# R203X.net
KiCad netlist of a schematic drawn in EAGLE
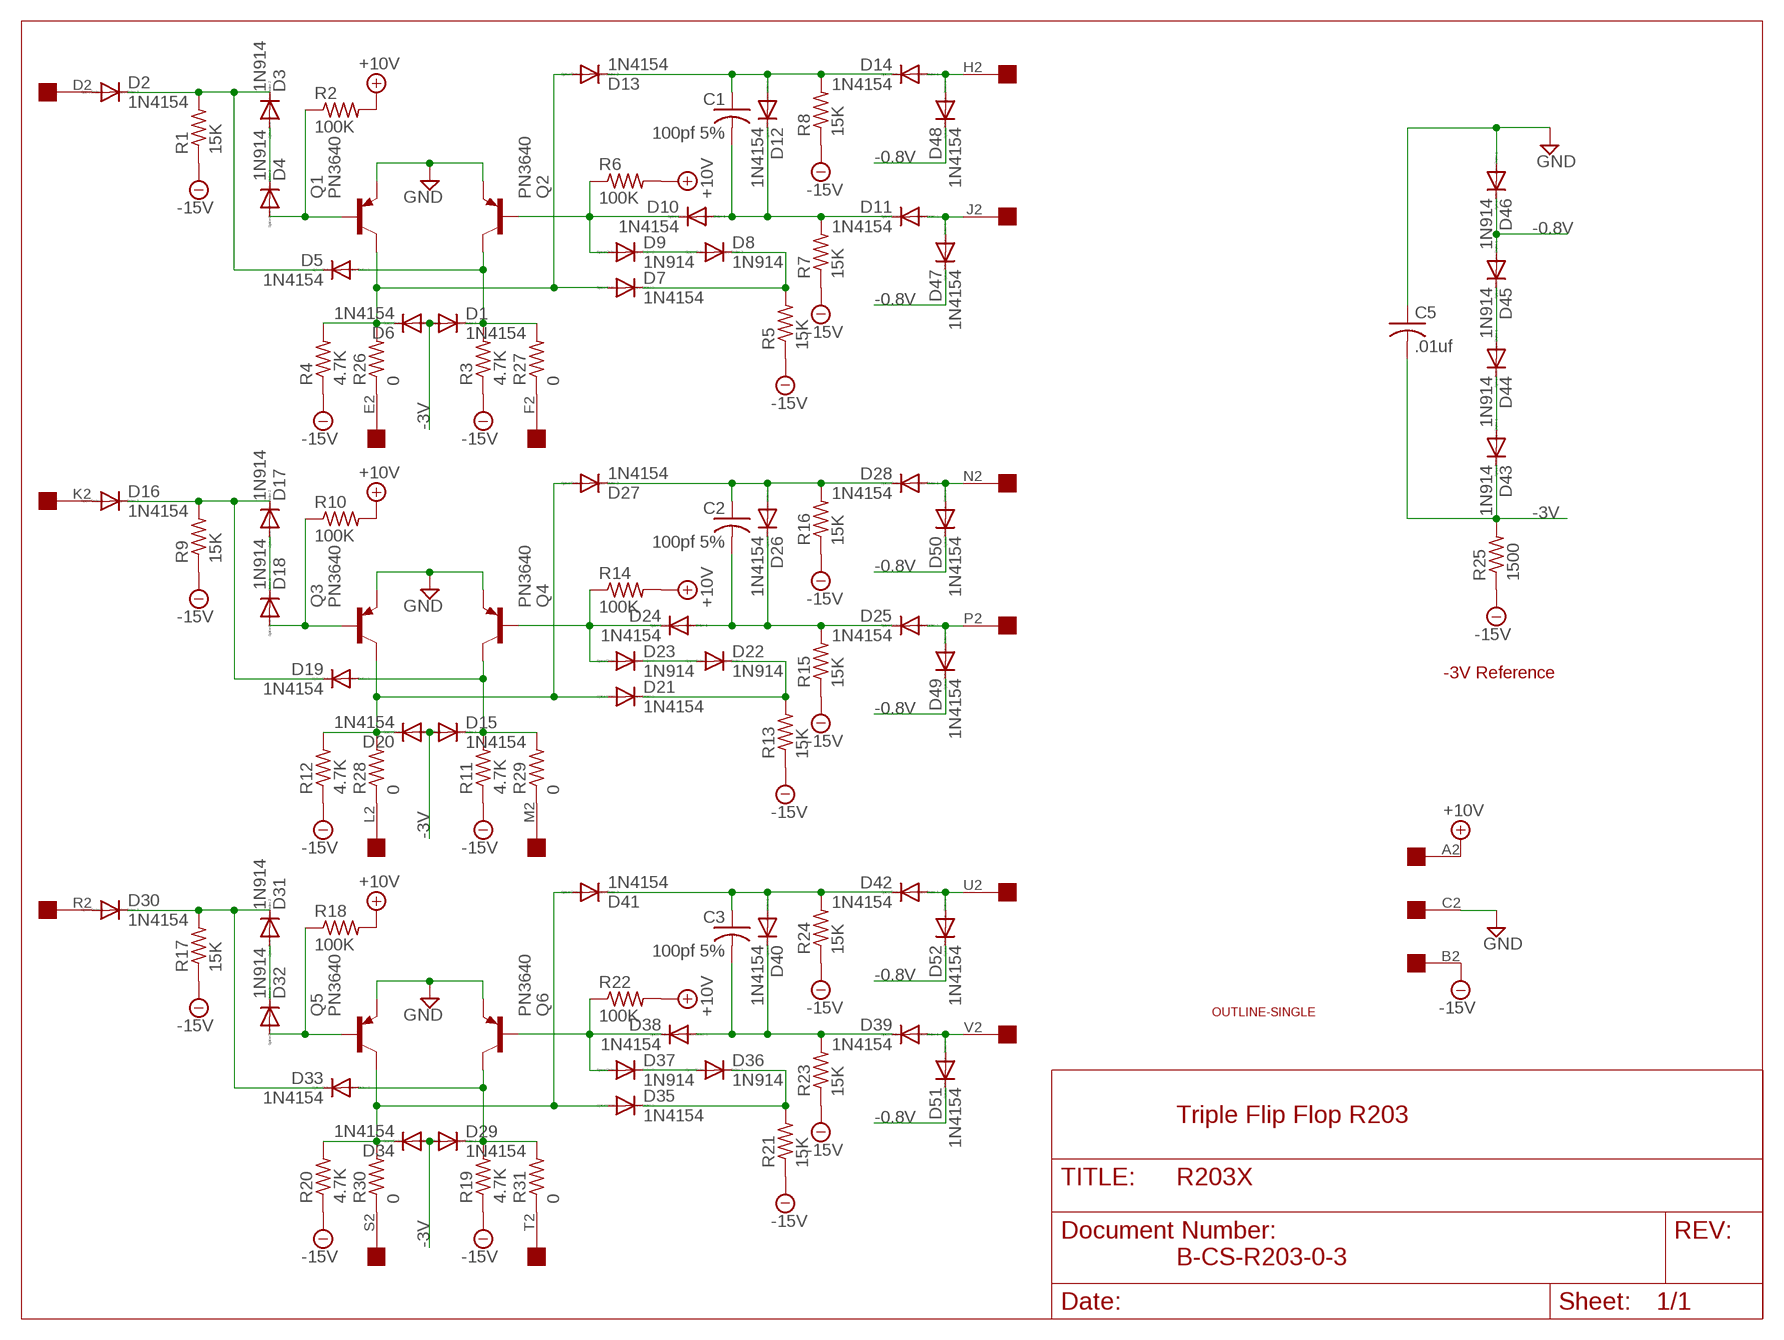
[diagram p0: schematic, sheet 1]

(export (version "E")
  (design (tool "Eeschema 10.0.6"))
  (components
    (comp (ref "C1")
      (value "100pf 5%")
      (footprint "eagle-import:C050-025X075")
      (libsource (lib "eagle-import") (part "C-US050-025X075"))
    )
    (comp (ref "C2")
      (value "100pf 5%")
      (footprint "eagle-import:C050-025X075")
      (libsource (lib "eagle-import") (part "C-US050-025X075"))
    )
    (comp (ref "C3")
      (value "100pf 5%")
      (footprint "eagle-import:C050-025X075")
      (libsource (lib "eagle-import") (part "C-US050-025X075"))
    )
    (comp (ref "C5")
      (value ".01uf")
      (footprint "eagle-import:C050-025X075")
      (libsource (lib "eagle-import") (part "C-US050-025X075"))
    )
    (comp (ref "D1")
      (value "1N4154")
      (footprint "eagle-import:DO35-10")
      (libsource (lib "eagle-import") (part "1N4148DO35-10"))
    )
    (comp (ref "D2")
      (value "1N4154")
      (footprint "eagle-import:DO35-10")
      (libsource (lib "eagle-import") (part "1N4148DO35-10"))
    )
    (comp (ref "D3")
      (value "1N914")
      (footprint "eagle-import:DO35-10")
      (libsource (lib "eagle-import") (part "1N4148DO35-10"))
    )
    (comp (ref "D4")
      (value "1N914")
      (footprint "eagle-import:DO35-10")
      (libsource (lib "eagle-import") (part "1N4148DO35-10"))
    )
    (comp (ref "D5")
      (value "1N4154")
      (footprint "eagle-import:DO35-10")
      (libsource (lib "eagle-import") (part "1N4148DO35-10"))
    )
    (comp (ref "D6")
      (value "1N4154")
      (footprint "eagle-import:DO35-10")
      (libsource (lib "eagle-import") (part "1N4148DO35-10"))
    )
    (comp (ref "D7")
      (value "1N4154")
      (footprint "eagle-import:DO35-10")
      (libsource (lib "eagle-import") (part "1N4148DO35-10"))
    )
    (comp (ref "D8")
      (value "1N914")
      (footprint "eagle-import:DO35-10")
      (libsource (lib "eagle-import") (part "1N4148DO35-10"))
    )
    (comp (ref "D9")
      (value "1N914")
      (footprint "eagle-import:DO35-10")
      (libsource (lib "eagle-import") (part "1N4148DO35-10"))
    )
    (comp (ref "D10")
      (value "1N4154")
      (footprint "eagle-import:DO35-10")
      (libsource (lib "eagle-import") (part "1N4148DO35-10"))
    )
    (comp (ref "D11")
      (value "1N4154")
      (footprint "eagle-import:DO35-10")
      (libsource (lib "eagle-import") (part "1N4148DO35-10"))
    )
    (comp (ref "D12")
      (value "1N4154")
      (footprint "eagle-import:DO35-10")
      (libsource (lib "eagle-import") (part "1N4148DO35-10"))
    )
    (comp (ref "D13")
      (value "1N4154")
      (footprint "eagle-import:DO35-10")
      (libsource (lib "eagle-import") (part "1N4148DO35-10"))
    )
    (comp (ref "D14")
      (value "1N4154")
      (footprint "eagle-import:DO35-10")
      (libsource (lib "eagle-import") (part "1N4148DO35-10"))
    )
    (comp (ref "D15")
      (value "1N4154")
      (footprint "eagle-import:DO35-10")
      (libsource (lib "eagle-import") (part "1N4148DO35-10"))
    )
    (comp (ref "D16")
      (value "1N4154")
      (footprint "eagle-import:DO35-10")
      (libsource (lib "eagle-import") (part "1N4148DO35-10"))
    )
    (comp (ref "D17")
      (value "1N914")
      (footprint "eagle-import:DO35-10")
      (libsource (lib "eagle-import") (part "1N4148DO35-10"))
    )
    (comp (ref "D18")
      (value "1N914")
      (footprint "eagle-import:DO35-10")
      (libsource (lib "eagle-import") (part "1N4148DO35-10"))
    )
    (comp (ref "D19")
      (value "1N4154")
      (footprint "eagle-import:DO35-10")
      (libsource (lib "eagle-import") (part "1N4148DO35-10"))
    )
    (comp (ref "D20")
      (value "1N4154")
      (footprint "eagle-import:DO35-10")
      (libsource (lib "eagle-import") (part "1N4148DO35-10"))
    )
    (comp (ref "D21")
      (value "1N4154")
      (footprint "eagle-import:DO35-10")
      (libsource (lib "eagle-import") (part "1N4148DO35-10"))
    )
    (comp (ref "D22")
      (value "1N914")
      (footprint "eagle-import:DO35-10")
      (libsource (lib "eagle-import") (part "1N4148DO35-10"))
    )
    (comp (ref "D23")
      (value "1N914")
      (footprint "eagle-import:DO35-10")
      (libsource (lib "eagle-import") (part "1N4148DO35-10"))
    )
    (comp (ref "D24")
      (value "1N4154")
      (footprint "eagle-import:DO35-10")
      (libsource (lib "eagle-import") (part "1N4148DO35-10"))
    )
    (comp (ref "D25")
      (value "1N4154")
      (footprint "eagle-import:DO35-10")
      (libsource (lib "eagle-import") (part "1N4148DO35-10"))
    )
    (comp (ref "D26")
      (value "1N4154")
      (footprint "eagle-import:DO35-10")
      (libsource (lib "eagle-import") (part "1N4148DO35-10"))
    )
    (comp (ref "D27")
      (value "1N4154")
      (footprint "eagle-import:DO35-10")
      (libsource (lib "eagle-import") (part "1N4148DO35-10"))
    )
    (comp (ref "D28")
      (value "1N4154")
      (footprint "eagle-import:DO35-10")
      (libsource (lib "eagle-import") (part "1N4148DO35-10"))
    )
    (comp (ref "D29")
      (value "1N4154")
      (footprint "eagle-import:DO35-10")
      (libsource (lib "eagle-import") (part "1N4148DO35-10"))
    )
    (comp (ref "D30")
      (value "1N4154")
      (footprint "eagle-import:DO35-10")
      (libsource (lib "eagle-import") (part "1N4148DO35-10"))
    )
    (comp (ref "D31")
      (value "1N914")
      (footprint "eagle-import:DO35-10")
      (libsource (lib "eagle-import") (part "1N4148DO35-10"))
    )
    (comp (ref "D32")
      (value "1N914")
      (footprint "eagle-import:DO35-10")
      (libsource (lib "eagle-import") (part "1N4148DO35-10"))
    )
    (comp (ref "D33")
      (value "1N4154")
      (footprint "eagle-import:DO35-10")
      (libsource (lib "eagle-import") (part "1N4148DO35-10"))
    )
    (comp (ref "D34")
      (value "1N4154")
      (footprint "eagle-import:DO35-10")
      (libsource (lib "eagle-import") (part "1N4148DO35-10"))
    )
    (comp (ref "D35")
      (value "1N4154")
      (footprint "eagle-import:DO35-10")
      (libsource (lib "eagle-import") (part "1N4148DO35-10"))
    )
    (comp (ref "D36")
      (value "1N914")
      (footprint "eagle-import:DO35-10")
      (libsource (lib "eagle-import") (part "1N4148DO35-10"))
    )
    (comp (ref "D37")
      (value "1N914")
      (footprint "eagle-import:DO35-10")
      (libsource (lib "eagle-import") (part "1N4148DO35-10"))
    )
    (comp (ref "D38")
      (value "1N4154")
      (footprint "eagle-import:DO35-10")
      (libsource (lib "eagle-import") (part "1N4148DO35-10"))
    )
    (comp (ref "D39")
      (value "1N4154")
      (footprint "eagle-import:DO35-10")
      (libsource (lib "eagle-import") (part "1N4148DO35-10"))
    )
    (comp (ref "D40")
      (value "1N4154")
      (footprint "eagle-import:DO35-10")
      (libsource (lib "eagle-import") (part "1N4148DO35-10"))
    )
    (comp (ref "D41")
      (value "1N4154")
      (footprint "eagle-import:DO35-10")
      (libsource (lib "eagle-import") (part "1N4148DO35-10"))
    )
    (comp (ref "D42")
      (value "1N4154")
      (footprint "eagle-import:DO35-10")
      (libsource (lib "eagle-import") (part "1N4148DO35-10"))
    )
    (comp (ref "D43")
      (value "1N914")
      (footprint "eagle-import:DO35-10")
      (libsource (lib "eagle-import") (part "1N4148DO35-10"))
    )
    (comp (ref "D44")
      (value "1N914")
      (footprint "eagle-import:DO35-10")
      (libsource (lib "eagle-import") (part "1N4148DO35-10"))
    )
    (comp (ref "D45")
      (value "1N914")
      (footprint "eagle-import:DO35-10")
      (libsource (lib "eagle-import") (part "1N4148DO35-10"))
    )
    (comp (ref "D46")
      (value "1N914")
      (footprint "eagle-import:DO35-10")
      (libsource (lib "eagle-import") (part "1N4148DO35-10"))
    )
    (comp (ref "D47")
      (value "1N4154")
      (footprint "eagle-import:DO35-10")
      (libsource (lib "eagle-import") (part "1N4148DO35-10"))
    )
    (comp (ref "D48")
      (value "1N4154")
      (footprint "eagle-import:DO35-10")
      (libsource (lib "eagle-import") (part "1N4148DO35-10"))
    )
    (comp (ref "D49")
      (value "1N4154")
      (footprint "eagle-import:DO35-10")
      (libsource (lib "eagle-import") (part "1N4148DO35-10"))
    )
    (comp (ref "D50")
      (value "1N4154")
      (footprint "eagle-import:DO35-10")
      (libsource (lib "eagle-import") (part "1N4148DO35-10"))
    )
    (comp (ref "D51")
      (value "1N4154")
      (footprint "eagle-import:DO35-10")
      (libsource (lib "eagle-import") (part "1N4148DO35-10"))
    )
    (comp (ref "D52")
      (value "1N4154")
      (footprint "eagle-import:DO35-10")
      (libsource (lib "eagle-import") (part "1N4148DO35-10"))
    )
    (comp (ref "Q1")
      (value "PN3640")
      (footprint "eagle-import:TO39")
      (libsource (lib "eagle-import") (part "2N3637"))
    )
    (comp (ref "Q2")
      (value "PN3640")
      (footprint "eagle-import:TO39")
      (libsource (lib "eagle-import") (part "2N3637"))
    )
    (comp (ref "Q3")
      (value "PN3640")
      (footprint "eagle-import:TO39")
      (libsource (lib "eagle-import") (part "2N3637"))
    )
    (comp (ref "Q4")
      (value "PN3640")
      (footprint "eagle-import:TO39")
      (libsource (lib "eagle-import") (part "2N3637"))
    )
    (comp (ref "Q5")
      (value "PN3640")
      (footprint "eagle-import:TO39")
      (libsource (lib "eagle-import") (part "2N3637"))
    )
    (comp (ref "Q6")
      (value "PN3640")
      (footprint "eagle-import:TO39")
      (libsource (lib "eagle-import") (part "2N3637"))
    )
    (comp (ref "R1")
      (value "15K")
      (footprint "eagle-import:0207_10")
      (libsource (lib "eagle-import") (part "R-US_0207/10"))
    )
    (comp (ref "R2")
      (value "100K")
      (footprint "eagle-import:0207_10")
      (libsource (lib "eagle-import") (part "R-US_0207/10"))
    )
    (comp (ref "R3")
      (value "4.7K")
      (footprint "eagle-import:0207_10")
      (libsource (lib "eagle-import") (part "R-US_0207/10"))
    )
    (comp (ref "R4")
      (value "4.7K")
      (footprint "eagle-import:0207_10")
      (libsource (lib "eagle-import") (part "R-US_0207/10"))
    )
    (comp (ref "R5")
      (value "15K")
      (footprint "eagle-import:0207_10")
      (libsource (lib "eagle-import") (part "R-US_0207/10"))
    )
    (comp (ref "R6")
      (value "100K")
      (footprint "eagle-import:0207_10")
      (libsource (lib "eagle-import") (part "R-US_0207/10"))
    )
    (comp (ref "R7")
      (value "15K")
      (footprint "eagle-import:0207_10")
      (libsource (lib "eagle-import") (part "R-US_0207/10"))
    )
    (comp (ref "R8")
      (value "15K")
      (footprint "eagle-import:0207_10")
      (libsource (lib "eagle-import") (part "R-US_0207/10"))
    )
    (comp (ref "R9")
      (value "15K")
      (footprint "eagle-import:0207_10")
      (libsource (lib "eagle-import") (part "R-US_0207/10"))
    )
    (comp (ref "R10")
      (value "100K")
      (footprint "eagle-import:0207_10")
      (libsource (lib "eagle-import") (part "R-US_0207/10"))
    )
    (comp (ref "R11")
      (value "4.7K")
      (footprint "eagle-import:0207_10")
      (libsource (lib "eagle-import") (part "R-US_0207/10"))
    )
    (comp (ref "R12")
      (value "4.7K")
      (footprint "eagle-import:0207_10")
      (libsource (lib "eagle-import") (part "R-US_0207/10"))
    )
    (comp (ref "R13")
      (value "15K")
      (footprint "eagle-import:0207_10")
      (libsource (lib "eagle-import") (part "R-US_0207/10"))
    )
    (comp (ref "R14")
      (value "100K")
      (footprint "eagle-import:0207_10")
      (libsource (lib "eagle-import") (part "R-US_0207/10"))
    )
    (comp (ref "R15")
      (value "15K")
      (footprint "eagle-import:0207_10")
      (libsource (lib "eagle-import") (part "R-US_0207/10"))
    )
    (comp (ref "R16")
      (value "15K")
      (footprint "eagle-import:0207_10")
      (libsource (lib "eagle-import") (part "R-US_0207/10"))
    )
    (comp (ref "R17")
      (value "15K")
      (footprint "eagle-import:0207_10")
      (libsource (lib "eagle-import") (part "R-US_0207/10"))
    )
    (comp (ref "R18")
      (value "100K")
      (footprint "eagle-import:0207_10")
      (libsource (lib "eagle-import") (part "R-US_0207/10"))
    )
    (comp (ref "R19")
      (value "4.7K")
      (footprint "eagle-import:0207_10")
      (libsource (lib "eagle-import") (part "R-US_0207/10"))
    )
    (comp (ref "R20")
      (value "4.7K")
      (footprint "eagle-import:0207_10")
      (libsource (lib "eagle-import") (part "R-US_0207/10"))
    )
    (comp (ref "R21")
      (value "15K")
      (footprint "eagle-import:0207_10")
      (libsource (lib "eagle-import") (part "R-US_0207/10"))
    )
    (comp (ref "R22")
      (value "100K")
      (footprint "eagle-import:0207_10")
      (libsource (lib "eagle-import") (part "R-US_0207/10"))
    )
    (comp (ref "R23")
      (value "15K")
      (footprint "eagle-import:0207_10")
      (libsource (lib "eagle-import") (part "R-US_0207/10"))
    )
    (comp (ref "R24")
      (value "15K")
      (footprint "eagle-import:0207_10")
      (libsource (lib "eagle-import") (part "R-US_0207/10"))
    )
    (comp (ref "R25")
      (value "1500")
      (footprint "eagle-import:0207_10")
      (libsource (lib "eagle-import") (part "R-US_0207/10"))
    )
    (comp (ref "R26")
      (value "0")
      (footprint "eagle-import:0207_10")
      (libsource (lib "eagle-import") (part "R-US_0207/10"))
    )
    (comp (ref "R27")
      (value "0")
      (footprint "eagle-import:0207_10")
      (libsource (lib "eagle-import") (part "R-US_0207/10"))
    )
    (comp (ref "R28")
      (value "0")
      (footprint "eagle-import:0207_10")
      (libsource (lib "eagle-import") (part "R-US_0207/10"))
    )
    (comp (ref "R29")
      (value "0")
      (footprint "eagle-import:0207_10")
      (libsource (lib "eagle-import") (part "R-US_0207/10"))
    )
    (comp (ref "R30")
      (value "0")
      (footprint "eagle-import:0207_10")
      (libsource (lib "eagle-import") (part "R-US_0207/10"))
    )
    (comp (ref "R31")
      (value "0")
      (footprint "eagle-import:0207_10")
      (libsource (lib "eagle-import") (part "R-US_0207/10"))
    )
    (comp (ref "U$1")
      (value "OUTLINE-SINGLE")
      (footprint "eagle-import:SINGLE")
      (libsource (lib "eagle-import") (part "OUTLINE-SINGLE"))
    )
    (comp (ref "U$2")
      (value "EDGE-1")
      (footprint "eagle-import:EDGE-CON1")
      (libsource (lib "eagle-import") (part "EDGE-1"))
    )
  )
  (nets
    (net (code "1") (name "+10V") (class "Default")
      (node (ref "R10") (pin "2") (pinfunction "2_2") (pintype "passive"))
      (node (ref "R14") (pin "2") (pinfunction "2_2") (pintype "passive"))
      (node (ref "R18") (pin "2") (pinfunction "2_2") (pintype "passive"))
      (node (ref "R2") (pin "2") (pinfunction "2_2") (pintype "passive"))
      (node (ref "R22") (pin "2") (pinfunction "2_2") (pintype "passive"))
      (node (ref "R6") (pin "2") (pinfunction "2_2") (pintype "passive"))
      (node (ref "U$2") (pin "A2") (pinfunction "1_A2") (pintype "bidirectional"))
    )
    (net (code "2") (name "-15V") (class "Default")
      (node (ref "R1") (pin "1") (pinfunction "1_1") (pintype "passive"))
      (node (ref "R11") (pin "1") (pinfunction "1_1") (pintype "passive"))
      (node (ref "R12") (pin "1") (pinfunction "1_1") (pintype "passive"))
      (node (ref "R13") (pin "1") (pinfunction "1_1") (pintype "passive"))
      (node (ref "R15") (pin "1") (pinfunction "1_1") (pintype "passive"))
      (node (ref "R16") (pin "1") (pinfunction "1_1") (pintype "passive"))
      (node (ref "R17") (pin "1") (pinfunction "1_1") (pintype "passive"))
      (node (ref "R19") (pin "1") (pinfunction "1_1") (pintype "passive"))
      (node (ref "R20") (pin "1") (pinfunction "1_1") (pintype "passive"))
      (node (ref "R21") (pin "1") (pinfunction "1_1") (pintype "passive"))
      (node (ref "R23") (pin "1") (pinfunction "1_1") (pintype "passive"))
      (node (ref "R24") (pin "1") (pinfunction "1_1") (pintype "passive"))
      (node (ref "R25") (pin "1") (pinfunction "1_1") (pintype "passive"))
      (node (ref "R3") (pin "1") (pinfunction "1_1") (pintype "passive"))
      (node (ref "R4") (pin "1") (pinfunction "1_1") (pintype "passive"))
      (node (ref "R5") (pin "1") (pinfunction "1_1") (pintype "passive"))
      (node (ref "R7") (pin "1") (pinfunction "1_1") (pintype "passive"))
      (node (ref "R8") (pin "1") (pinfunction "1_1") (pintype "passive"))
      (node (ref "R9") (pin "1") (pinfunction "1_1") (pintype "passive"))
      (node (ref "U$2") (pin "B2") (pinfunction "1_B2") (pintype "bidirectional"))
    )
    (net (code "3") (name "/-0.8V") (class "Default")
      (node (ref "D45") (pin "A") (pinfunction "A_A") (pintype "passive"))
      (node (ref "D46") (pin "C") (pinfunction "C_C") (pintype "passive"))
      (node (ref "D47") (pin "C") (pinfunction "C_C") (pintype "passive"))
      (node (ref "D48") (pin "C") (pinfunction "C_C") (pintype "passive"))
      (node (ref "D49") (pin "C") (pinfunction "C_C") (pintype "passive"))
      (node (ref "D50") (pin "C") (pinfunction "C_C") (pintype "passive"))
      (node (ref "D51") (pin "C") (pinfunction "C_C") (pintype "passive"))
      (node (ref "D52") (pin "C") (pinfunction "C_C") (pintype "passive"))
    )
    (net (code "4") (name "/-3V") (class "Default")
      (node (ref "C5") (pin "2") (pinfunction "2_2") (pintype "passive"))
      (node (ref "D1") (pin "A") (pinfunction "A_A") (pintype "passive"))
      (node (ref "D15") (pin "A") (pinfunction "A_A") (pintype "passive"))
      (node (ref "D20") (pin "A") (pinfunction "A_A") (pintype "passive"))
      (node (ref "D29") (pin "A") (pinfunction "A_A") (pintype "passive"))
      (node (ref "D34") (pin "A") (pinfunction "A_A") (pintype "passive"))
      (node (ref "D43") (pin "C") (pinfunction "C_C") (pintype "passive"))
      (node (ref "D6") (pin "A") (pinfunction "A_A") (pintype "passive"))
      (node (ref "R25") (pin "2") (pinfunction "2_2") (pintype "passive"))
    )
    (net (code "5") (name "GND") (class "Default")
      (node (ref "C5") (pin "1") (pinfunction "1_1") (pintype "passive"))
      (node (ref "D46") (pin "A") (pinfunction "A_A") (pintype "passive"))
      (node (ref "Q1") (pin "1") (pinfunction "E_1") (pintype "passive"))
      (node (ref "Q2") (pin "1") (pinfunction "E_1") (pintype "passive"))
      (node (ref "Q3") (pin "1") (pinfunction "E_1") (pintype "passive"))
      (node (ref "Q4") (pin "1") (pinfunction "E_1") (pintype "passive"))
      (node (ref "Q5") (pin "1") (pinfunction "E_1") (pintype "passive"))
      (node (ref "Q6") (pin "1") (pinfunction "E_1") (pintype "passive"))
      (node (ref "U$2") (pin "C2") (pinfunction "1_C2") (pintype "bidirectional"))
    )
    (net (code "6") (name "Net-(C1-Pad1)") (class "Default")
      (node (ref "C1") (pin "1") (pinfunction "1_1") (pintype "passive"))
      (node (ref "D12") (pin "A") (pinfunction "A_A") (pintype "passive"))
      (node (ref "D13") (pin "C") (pinfunction "C_C") (pintype "passive"))
      (node (ref "D14") (pin "C") (pinfunction "C_C") (pintype "passive"))
      (node (ref "R8") (pin "2") (pinfunction "2_2") (pintype "passive"))
    )
    (net (code "7") (name "Net-(C1-Pad2)") (class "Default")
      (node (ref "C1") (pin "2") (pinfunction "2_2") (pintype "passive"))
      (node (ref "D10") (pin "A") (pinfunction "A_A") (pintype "passive"))
      (node (ref "D11") (pin "C") (pinfunction "C_C") (pintype "passive"))
      (node (ref "D12") (pin "C") (pinfunction "C_C") (pintype "passive"))
      (node (ref "R7") (pin "2") (pinfunction "2_2") (pintype "passive"))
    )
    (net (code "8") (name "Net-(C2-Pad1)") (class "Default")
      (node (ref "C2") (pin "1") (pinfunction "1_1") (pintype "passive"))
      (node (ref "D26") (pin "A") (pinfunction "A_A") (pintype "passive"))
      (node (ref "D27") (pin "C") (pinfunction "C_C") (pintype "passive"))
      (node (ref "D28") (pin "C") (pinfunction "C_C") (pintype "passive"))
      (node (ref "R16") (pin "2") (pinfunction "2_2") (pintype "passive"))
    )
    (net (code "9") (name "Net-(C2-Pad2)") (class "Default")
      (node (ref "C2") (pin "2") (pinfunction "2_2") (pintype "passive"))
      (node (ref "D24") (pin "A") (pinfunction "A_A") (pintype "passive"))
      (node (ref "D25") (pin "C") (pinfunction "C_C") (pintype "passive"))
      (node (ref "D26") (pin "C") (pinfunction "C_C") (pintype "passive"))
      (node (ref "R15") (pin "2") (pinfunction "2_2") (pintype "passive"))
    )
    (net (code "10") (name "Net-(C3-Pad1)") (class "Default")
      (node (ref "C3") (pin "1") (pinfunction "1_1") (pintype "passive"))
      (node (ref "D40") (pin "A") (pinfunction "A_A") (pintype "passive"))
      (node (ref "D41") (pin "C") (pinfunction "C_C") (pintype "passive"))
      (node (ref "D42") (pin "C") (pinfunction "C_C") (pintype "passive"))
      (node (ref "R24") (pin "2") (pinfunction "2_2") (pintype "passive"))
    )
    (net (code "11") (name "Net-(C3-Pad2)") (class "Default")
      (node (ref "C3") (pin "2") (pinfunction "2_2") (pintype "passive"))
      (node (ref "D38") (pin "A") (pinfunction "A_A") (pintype "passive"))
      (node (ref "D39") (pin "C") (pinfunction "C_C") (pintype "passive"))
      (node (ref "D40") (pin "C") (pinfunction "C_C") (pintype "passive"))
      (node (ref "R23") (pin "2") (pinfunction "2_2") (pintype "passive"))
    )
    (net (code "12") (name "Net-(D2-PadC)") (class "Default")
      (node (ref "D2") (pin "C") (pinfunction "C_C") (pintype "passive"))
      (node (ref "D3") (pin "C") (pinfunction "C_C") (pintype "passive"))
      (node (ref "D5") (pin "C") (pinfunction "C_C") (pintype "passive"))
      (node (ref "R1") (pin "2") (pinfunction "2_2") (pintype "passive"))
    )
    (net (code "13") (name "Net-(D3-PadA)") (class "Default")
      (node (ref "D3") (pin "A") (pinfunction "A_A") (pintype "passive"))
      (node (ref "D4") (pin "C") (pinfunction "C_C") (pintype "passive"))
    )
    (net (code "14") (name "Net-(D7-PadC)") (class "Default")
      (node (ref "D7") (pin "C") (pinfunction "C_C") (pintype "passive"))
      (node (ref "D8") (pin "C") (pinfunction "C_C") (pintype "passive"))
      (node (ref "R5") (pin "2") (pinfunction "2_2") (pintype "passive"))
    )
    (net (code "15") (name "Net-(D8-PadA)") (class "Default")
      (node (ref "D8") (pin "A") (pinfunction "A_A") (pintype "passive"))
      (node (ref "D9") (pin "C") (pinfunction "C_C") (pintype "passive"))
    )
    (net (code "16") (name "Net-(D16-PadC)") (class "Default")
      (node (ref "D16") (pin "C") (pinfunction "C_C") (pintype "passive"))
      (node (ref "D17") (pin "C") (pinfunction "C_C") (pintype "passive"))
      (node (ref "D19") (pin "C") (pinfunction "C_C") (pintype "passive"))
      (node (ref "R9") (pin "2") (pinfunction "2_2") (pintype "passive"))
    )
    (net (code "17") (name "Net-(D17-PadA)") (class "Default")
      (node (ref "D17") (pin "A") (pinfunction "A_A") (pintype "passive"))
      (node (ref "D18") (pin "C") (pinfunction "C_C") (pintype "passive"))
    )
    (net (code "18") (name "Net-(D21-PadC)") (class "Default")
      (node (ref "D21") (pin "C") (pinfunction "C_C") (pintype "passive"))
      (node (ref "D22") (pin "C") (pinfunction "C_C") (pintype "passive"))
      (node (ref "R13") (pin "2") (pinfunction "2_2") (pintype "passive"))
    )
    (net (code "19") (name "Net-(D22-PadA)") (class "Default")
      (node (ref "D22") (pin "A") (pinfunction "A_A") (pintype "passive"))
      (node (ref "D23") (pin "C") (pinfunction "C_C") (pintype "passive"))
    )
    (net (code "20") (name "Net-(D30-PadC)") (class "Default")
      (node (ref "D30") (pin "C") (pinfunction "C_C") (pintype "passive"))
      (node (ref "D31") (pin "C") (pinfunction "C_C") (pintype "passive"))
      (node (ref "D33") (pin "C") (pinfunction "C_C") (pintype "passive"))
      (node (ref "R17") (pin "2") (pinfunction "2_2") (pintype "passive"))
    )
    (net (code "21") (name "Net-(D31-PadA)") (class "Default")
      (node (ref "D31") (pin "A") (pinfunction "A_A") (pintype "passive"))
      (node (ref "D32") (pin "C") (pinfunction "C_C") (pintype "passive"))
    )
    (net (code "22") (name "Net-(D35-PadC)") (class "Default")
      (node (ref "D35") (pin "C") (pinfunction "C_C") (pintype "passive"))
      (node (ref "D36") (pin "C") (pinfunction "C_C") (pintype "passive"))
      (node (ref "R21") (pin "2") (pinfunction "2_2") (pintype "passive"))
    )
    (net (code "23") (name "Net-(D36-PadA)") (class "Default")
      (node (ref "D36") (pin "A") (pinfunction "A_A") (pintype "passive"))
      (node (ref "D37") (pin "C") (pinfunction "C_C") (pintype "passive"))
    )
    (net (code "24") (name "Net-(D43-PadA)") (class "Default")
      (node (ref "D43") (pin "A") (pinfunction "A_A") (pintype "passive"))
      (node (ref "D44") (pin "C") (pinfunction "C_C") (pintype "passive"))
    )
    (net (code "25") (name "Net-(D44-PadA)") (class "Default")
      (node (ref "D44") (pin "A") (pinfunction "A_A") (pintype "passive"))
      (node (ref "D45") (pin "C") (pinfunction "C_C") (pintype "passive"))
    )
    (net (code "26") (name "Net-(Q1-B)") (class "Default")
      (node (ref "D4") (pin "A") (pinfunction "A_A") (pintype "passive"))
      (node (ref "Q1") (pin "2") (pinfunction "B_2") (pintype "passive"))
      (node (ref "R2") (pin "1") (pinfunction "1_1") (pintype "passive"))
    )
    (net (code "27") (name "Net-(Q1-C)") (class "Default")
      (node (ref "D13") (pin "A") (pinfunction "A_A") (pintype "passive"))
      (node (ref "D6") (pin "C") (pinfunction "C_C") (pintype "passive"))
      (node (ref "D7") (pin "A") (pinfunction "A_A") (pintype "passive"))
      (node (ref "Q1") (pin "3") (pinfunction "C_3") (pintype "passive"))
      (node (ref "R26") (pin "2") (pinfunction "2_2") (pintype "passive"))
      (node (ref "R4") (pin "2") (pinfunction "2_2") (pintype "passive"))
    )
    (net (code "28") (name "Net-(Q2-B)") (class "Default")
      (node (ref "D10") (pin "C") (pinfunction "C_C") (pintype "passive"))
      (node (ref "D9") (pin "A") (pinfunction "A_A") (pintype "passive"))
      (node (ref "Q2") (pin "2") (pinfunction "B_2") (pintype "passive"))
      (node (ref "R6") (pin "1") (pinfunction "1_1") (pintype "passive"))
    )
    (net (code "29") (name "Net-(Q2-C)") (class "Default")
      (node (ref "D1") (pin "C") (pinfunction "C_C") (pintype "passive"))
      (node (ref "D5") (pin "A") (pinfunction "A_A") (pintype "passive"))
      (node (ref "Q2") (pin "3") (pinfunction "C_3") (pintype "passive"))
      (node (ref "R27") (pin "2") (pinfunction "2_2") (pintype "passive"))
      (node (ref "R3") (pin "2") (pinfunction "2_2") (pintype "passive"))
    )
    (net (code "30") (name "Net-(Q3-B)") (class "Default")
      (node (ref "D18") (pin "A") (pinfunction "A_A") (pintype "passive"))
      (node (ref "Q3") (pin "2") (pinfunction "B_2") (pintype "passive"))
      (node (ref "R10") (pin "1") (pinfunction "1_1") (pintype "passive"))
    )
    (net (code "31") (name "Net-(Q3-C)") (class "Default")
      (node (ref "D20") (pin "C") (pinfunction "C_C") (pintype "passive"))
      (node (ref "D21") (pin "A") (pinfunction "A_A") (pintype "passive"))
      (node (ref "D27") (pin "A") (pinfunction "A_A") (pintype "passive"))
      (node (ref "Q3") (pin "3") (pinfunction "C_3") (pintype "passive"))
      (node (ref "R12") (pin "2") (pinfunction "2_2") (pintype "passive"))
      (node (ref "R28") (pin "2") (pinfunction "2_2") (pintype "passive"))
    )
    (net (code "32") (name "Net-(Q4-B)") (class "Default")
      (node (ref "D23") (pin "A") (pinfunction "A_A") (pintype "passive"))
      (node (ref "D24") (pin "C") (pinfunction "C_C") (pintype "passive"))
      (node (ref "Q4") (pin "2") (pinfunction "B_2") (pintype "passive"))
      (node (ref "R14") (pin "1") (pinfunction "1_1") (pintype "passive"))
    )
    (net (code "33") (name "Net-(Q4-C)") (class "Default")
      (node (ref "D15") (pin "C") (pinfunction "C_C") (pintype "passive"))
      (node (ref "D19") (pin "A") (pinfunction "A_A") (pintype "passive"))
      (node (ref "Q4") (pin "3") (pinfunction "C_3") (pintype "passive"))
      (node (ref "R11") (pin "2") (pinfunction "2_2") (pintype "passive"))
      (node (ref "R29") (pin "2") (pinfunction "2_2") (pintype "passive"))
    )
    (net (code "34") (name "Net-(Q5-B)") (class "Default")
      (node (ref "D32") (pin "A") (pinfunction "A_A") (pintype "passive"))
      (node (ref "Q5") (pin "2") (pinfunction "B_2") (pintype "passive"))
      (node (ref "R18") (pin "1") (pinfunction "1_1") (pintype "passive"))
    )
    (net (code "35") (name "Net-(Q5-C)") (class "Default")
      (node (ref "D34") (pin "C") (pinfunction "C_C") (pintype "passive"))
      (node (ref "D35") (pin "A") (pinfunction "A_A") (pintype "passive"))
      (node (ref "D41") (pin "A") (pinfunction "A_A") (pintype "passive"))
      (node (ref "Q5") (pin "3") (pinfunction "C_3") (pintype "passive"))
      (node (ref "R20") (pin "2") (pinfunction "2_2") (pintype "passive"))
      (node (ref "R30") (pin "2") (pinfunction "2_2") (pintype "passive"))
    )
    (net (code "36") (name "Net-(Q6-B)") (class "Default")
      (node (ref "D37") (pin "A") (pinfunction "A_A") (pintype "passive"))
      (node (ref "D38") (pin "C") (pinfunction "C_C") (pintype "passive"))
      (node (ref "Q6") (pin "2") (pinfunction "B_2") (pintype "passive"))
      (node (ref "R22") (pin "1") (pinfunction "1_1") (pintype "passive"))
    )
    (net (code "37") (name "Net-(Q6-C)") (class "Default")
      (node (ref "D29") (pin "C") (pinfunction "C_C") (pintype "passive"))
      (node (ref "D33") (pin "A") (pinfunction "A_A") (pintype "passive"))
      (node (ref "Q6") (pin "3") (pinfunction "C_3") (pintype "passive"))
      (node (ref "R19") (pin "2") (pinfunction "2_2") (pintype "passive"))
      (node (ref "R31") (pin "2") (pinfunction "2_2") (pintype "passive"))
    )
    (net (code "38") (name "Net-(U$2D-1)") (class "Default")
      (node (ref "D2") (pin "A") (pinfunction "A_A") (pintype "passive"))
      (node (ref "U$2") (pin "D2") (pinfunction "1_D2") (pintype "bidirectional"))
    )
    (net (code "39") (name "Net-(U$2E-1)") (class "Default")
      (node (ref "R26") (pin "1") (pinfunction "1_1") (pintype "passive"))
      (node (ref "U$2") (pin "E2") (pinfunction "1_E2") (pintype "bidirectional"))
    )
    (net (code "40") (name "Net-(U$2F-1)") (class "Default")
      (node (ref "R27") (pin "1") (pinfunction "1_1") (pintype "passive"))
      (node (ref "U$2") (pin "F2") (pinfunction "1_F2") (pintype "bidirectional"))
    )
    (net (code "41") (name "Net-(U$2G-1)") (class "Default")
      (node (ref "D14") (pin "A") (pinfunction "A_A") (pintype "passive"))
      (node (ref "D48") (pin "A") (pinfunction "A_A") (pintype "passive"))
      (node (ref "U$2") (pin "H2") (pinfunction "1_H2") (pintype "bidirectional"))
    )
    (net (code "42") (name "Net-(U$2H-1)") (class "Default")
      (node (ref "D11") (pin "A") (pinfunction "A_A") (pintype "passive"))
      (node (ref "D47") (pin "A") (pinfunction "A_A") (pintype "passive"))
      (node (ref "U$2") (pin "J2") (pinfunction "1_J2") (pintype "bidirectional"))
    )
    (net (code "43") (name "Net-(U$2I-1)") (class "Default")
      (node (ref "D16") (pin "A") (pinfunction "A_A") (pintype "passive"))
      (node (ref "U$2") (pin "K2") (pinfunction "1_K2") (pintype "bidirectional"))
    )
    (net (code "44") (name "Net-(U$2J-1)") (class "Default")
      (node (ref "R28") (pin "1") (pinfunction "1_1") (pintype "passive"))
      (node (ref "U$2") (pin "L2") (pinfunction "1_L2") (pintype "bidirectional"))
    )
    (net (code "45") (name "Net-(U$2K-1)") (class "Default")
      (node (ref "R29") (pin "1") (pinfunction "1_1") (pintype "passive"))
      (node (ref "U$2") (pin "M2") (pinfunction "1_M2") (pintype "bidirectional"))
    )
    (net (code "46") (name "Net-(U$2L-1)") (class "Default")
      (node (ref "D28") (pin "A") (pinfunction "A_A") (pintype "passive"))
      (node (ref "D50") (pin "A") (pinfunction "A_A") (pintype "passive"))
      (node (ref "U$2") (pin "N2") (pinfunction "1_N2") (pintype "bidirectional"))
    )
    (net (code "47") (name "Net-(U$2M-1)") (class "Default")
      (node (ref "D25") (pin "A") (pinfunction "A_A") (pintype "passive"))
      (node (ref "D49") (pin "A") (pinfunction "A_A") (pintype "passive"))
      (node (ref "U$2") (pin "P2") (pinfunction "1_P2") (pintype "bidirectional"))
    )
    (net (code "48") (name "Net-(U$2N-1)") (class "Default")
      (node (ref "D30") (pin "A") (pinfunction "A_A") (pintype "passive"))
      (node (ref "U$2") (pin "R2") (pinfunction "1_R2") (pintype "bidirectional"))
    )
    (net (code "49") (name "Net-(U$2O-1)") (class "Default")
      (node (ref "R30") (pin "1") (pinfunction "1_1") (pintype "passive"))
      (node (ref "U$2") (pin "S2") (pinfunction "1_S2") (pintype "bidirectional"))
    )
    (net (code "50") (name "Net-(U$2P-1)") (class "Default")
      (node (ref "R31") (pin "1") (pinfunction "1_1") (pintype "passive"))
      (node (ref "U$2") (pin "T2") (pinfunction "1_T2") (pintype "bidirectional"))
    )
    (net (code "51") (name "Net-(U$2Q-1)") (class "Default")
      (node (ref "D42") (pin "A") (pinfunction "A_A") (pintype "passive"))
      (node (ref "D52") (pin "A") (pinfunction "A_A") (pintype "passive"))
      (node (ref "U$2") (pin "U2") (pinfunction "1_U2") (pintype "bidirectional"))
    )
    (net (code "52") (name "Net-(U$2R-1)") (class "Default")
      (node (ref "D39") (pin "A") (pinfunction "A_A") (pintype "passive"))
      (node (ref "D51") (pin "A") (pinfunction "A_A") (pintype "passive"))
      (node (ref "U$2") (pin "V2") (pinfunction "1_V2") (pintype "bidirectional"))
    )
  )
)
